# rt_hirose_breakout.net
KiCad netlist of a schematic drawn in EAGLE
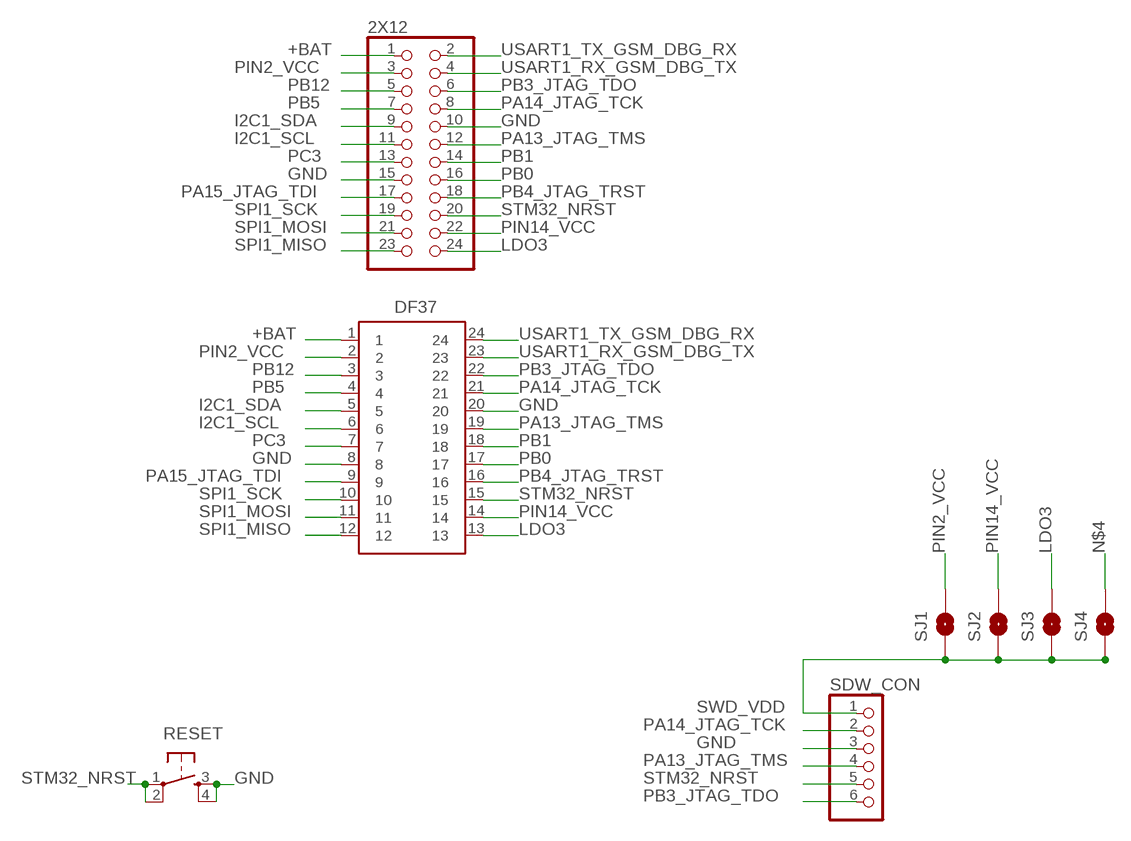
[diagram p0: schematic, sheet 1]

(export (version "E")
  (design (tool "Eeschema 10.0.6"))
  (components
    (comp (ref "2X12")
      (value "PINHD-2X12")
      (footprint "eagle-import:2X12")
      (libsource (lib "eagle-import") (part "PINHD-2X12"))
    )
    (comp (ref "DF37")
      (value "DF37-24-HEADER")
      (footprint "eagle-import:DF37-24-HEADER")
      (libsource (lib "eagle-import") (part "DF37-24-HEADER"))
    )
    (comp (ref "RESET")
      (value "TAC_SWITCHSMD")
      (footprint "eagle-import:TACTILE_SWITCH_SMD")
      (libsource (lib "eagle-import") (part "TAC_SWITCHSMD"))
    )
    (comp (ref "SDW_CON")
      (value "PINHD-1X6")
      (footprint "eagle-import:1X06")
      (libsource (lib "eagle-import") (part "PINHD-1X6"))
    )
    (comp (ref "SJ1")
      (value "SOLDERJUMPERNO")
      (footprint "eagle-import:SJ_2S-NO")
      (libsource (lib "eagle-import") (part "SOLDERJUMPERNO"))
    )
    (comp (ref "SJ2")
      (value "SOLDERJUMPERNO")
      (footprint "eagle-import:SJ_2S-NO")
      (libsource (lib "eagle-import") (part "SOLDERJUMPERNO"))
    )
    (comp (ref "SJ3")
      (value "SOLDERJUMPERNO")
      (footprint "eagle-import:SJ_2S-NO")
      (libsource (lib "eagle-import") (part "SOLDERJUMPERNO"))
    )
    (comp (ref "SJ4")
      (value "SOLDERJUMPERNO")
      (footprint "eagle-import:SJ_2S-NO")
      (libsource (lib "eagle-import") (part "SOLDERJUMPERNO"))
    )
  )
  (nets
    (net (code "1") (name "/+BAT") (class "Default")
      (node (ref "2X12") (pin "1") (pinfunction "1_1") (pintype "passive"))
      (node (ref "DF37") (pin "1") (pinfunction "1_1") (pintype "bidirectional"))
    )
    (net (code "2") (name "/GND") (class "Default")
      (node (ref "2X12") (pin "10") (pinfunction "10_10") (pintype "passive"))
      (node (ref "2X12") (pin "15") (pinfunction "15_15") (pintype "passive"))
      (node (ref "DF37") (pin "20") (pinfunction "20_20") (pintype "bidirectional"))
      (node (ref "DF37") (pin "8") (pinfunction "8_8") (pintype "bidirectional"))
      (node (ref "RESET") (pin "3") (pinfunction "3_3") (pintype "passive"))
      (node (ref "RESET") (pin "4") (pinfunction "4_4") (pintype "passive"))
      (node (ref "SDW_CON") (pin "3") (pinfunction "3_3") (pintype "passive"))
    )
    (net (code "3") (name "/I2C1_SCL") (class "Default")
      (node (ref "2X12") (pin "11") (pinfunction "11_11") (pintype "passive"))
      (node (ref "DF37") (pin "6") (pinfunction "6_6") (pintype "bidirectional"))
    )
    (net (code "4") (name "/I2C1_SDA") (class "Default")
      (node (ref "2X12") (pin "9") (pinfunction "9_9") (pintype "passive"))
      (node (ref "DF37") (pin "5") (pinfunction "5_5") (pintype "bidirectional"))
    )
    (net (code "5") (name "/LDO3") (class "Default")
      (node (ref "2X12") (pin "24") (pinfunction "24_24") (pintype "passive"))
      (node (ref "DF37") (pin "13") (pinfunction "13_13") (pintype "bidirectional"))
      (node (ref "SJ3") (pin "2") (pinfunction "2_2") (pintype "passive"))
    )
    (net (code "6") (name "/N$4") (class "Default")
      (node (ref "SJ4") (pin "2") (pinfunction "2_2") (pintype "passive"))
    )
    (net (code "7") (name "/PA13_JTAG_TMS") (class "Default")
      (node (ref "2X12") (pin "12") (pinfunction "12_12") (pintype "passive"))
      (node (ref "DF37") (pin "19") (pinfunction "19_19") (pintype "bidirectional"))
      (node (ref "SDW_CON") (pin "4") (pinfunction "4_4") (pintype "passive"))
    )
    (net (code "8") (name "/PA14_JTAG_TCK") (class "Default")
      (node (ref "2X12") (pin "8") (pinfunction "8_8") (pintype "passive"))
      (node (ref "DF37") (pin "21") (pinfunction "21_21") (pintype "bidirectional"))
      (node (ref "SDW_CON") (pin "2") (pinfunction "2_2") (pintype "passive"))
    )
    (net (code "9") (name "/PA15_JTAG_TDI") (class "Default")
      (node (ref "2X12") (pin "17") (pinfunction "17_17") (pintype "passive"))
      (node (ref "DF37") (pin "9") (pinfunction "9_9") (pintype "bidirectional"))
    )
    (net (code "10") (name "/PB0") (class "Default")
      (node (ref "2X12") (pin "16") (pinfunction "16_16") (pintype "passive"))
      (node (ref "DF37") (pin "17") (pinfunction "17_17") (pintype "bidirectional"))
    )
    (net (code "11") (name "/PB1") (class "Default")
      (node (ref "2X12") (pin "14") (pinfunction "14_14") (pintype "passive"))
      (node (ref "DF37") (pin "18") (pinfunction "18_18") (pintype "bidirectional"))
    )
    (net (code "12") (name "/PB3_JTAG_TDO") (class "Default")
      (node (ref "2X12") (pin "6") (pinfunction "6_6") (pintype "passive"))
      (node (ref "DF37") (pin "22") (pinfunction "22_22") (pintype "bidirectional"))
      (node (ref "SDW_CON") (pin "6") (pinfunction "6_6") (pintype "passive"))
    )
    (net (code "13") (name "/PB4_JTAG_TRST") (class "Default")
      (node (ref "2X12") (pin "18") (pinfunction "18_18") (pintype "passive"))
      (node (ref "DF37") (pin "16") (pinfunction "16_16") (pintype "bidirectional"))
    )
    (net (code "14") (name "/PB5") (class "Default")
      (node (ref "2X12") (pin "7") (pinfunction "7_7") (pintype "passive"))
      (node (ref "DF37") (pin "4") (pinfunction "4_4") (pintype "bidirectional"))
    )
    (net (code "15") (name "/PB12") (class "Default")
      (node (ref "2X12") (pin "5") (pinfunction "5_5") (pintype "passive"))
      (node (ref "DF37") (pin "3") (pinfunction "3_3") (pintype "bidirectional"))
    )
    (net (code "16") (name "/PC3") (class "Default")
      (node (ref "2X12") (pin "13") (pinfunction "13_13") (pintype "passive"))
      (node (ref "DF37") (pin "7") (pinfunction "7_7") (pintype "bidirectional"))
    )
    (net (code "17") (name "/PIN2_VCC") (class "Default")
      (node (ref "2X12") (pin "3") (pinfunction "3_3") (pintype "passive"))
      (node (ref "DF37") (pin "2") (pinfunction "2_2") (pintype "bidirectional"))
      (node (ref "SJ1") (pin "2") (pinfunction "2_2") (pintype "passive"))
    )
    (net (code "18") (name "/PIN14_VCC") (class "Default")
      (node (ref "2X12") (pin "22") (pinfunction "22_22") (pintype "passive"))
      (node (ref "DF37") (pin "14") (pinfunction "14_14") (pintype "bidirectional"))
      (node (ref "SJ2") (pin "2") (pinfunction "2_2") (pintype "passive"))
    )
    (net (code "19") (name "/SPI1_MISO") (class "Default")
      (node (ref "2X12") (pin "23") (pinfunction "23_23") (pintype "passive"))
      (node (ref "DF37") (pin "12") (pinfunction "12_12") (pintype "bidirectional"))
    )
    (net (code "20") (name "/SPI1_MOSI") (class "Default")
      (node (ref "2X12") (pin "21") (pinfunction "21_21") (pintype "passive"))
      (node (ref "DF37") (pin "11") (pinfunction "11_11") (pintype "bidirectional"))
    )
    (net (code "21") (name "/SPI1_SCK") (class "Default")
      (node (ref "2X12") (pin "19") (pinfunction "19_19") (pintype "passive"))
      (node (ref "DF37") (pin "10") (pinfunction "10_10") (pintype "bidirectional"))
    )
    (net (code "22") (name "/STM32_NRST") (class "Default")
      (node (ref "2X12") (pin "20") (pinfunction "20_20") (pintype "passive"))
      (node (ref "DF37") (pin "15") (pinfunction "15_15") (pintype "bidirectional"))
      (node (ref "RESET") (pin "1") (pinfunction "1_1") (pintype "passive"))
      (node (ref "RESET") (pin "2") (pinfunction "2_2") (pintype "passive"))
      (node (ref "SDW_CON") (pin "5") (pinfunction "5_5") (pintype "passive"))
    )
    (net (code "23") (name "/SWD_VDD") (class "Default")
      (node (ref "SDW_CON") (pin "1") (pinfunction "1_1") (pintype "passive"))
      (node (ref "SJ1") (pin "1") (pinfunction "1_1") (pintype "passive"))
      (node (ref "SJ2") (pin "1") (pinfunction "1_1") (pintype "passive"))
      (node (ref "SJ3") (pin "1") (pinfunction "1_1") (pintype "passive"))
      (node (ref "SJ4") (pin "1") (pinfunction "1_1") (pintype "passive"))
    )
    (net (code "24") (name "/USART1_RX_GSM_DBG_TX") (class "Default")
      (node (ref "2X12") (pin "4") (pinfunction "4_4") (pintype "passive"))
      (node (ref "DF37") (pin "23") (pinfunction "23_23") (pintype "bidirectional"))
    )
    (net (code "25") (name "/USART1_TX_GSM_DBG_RX") (class "Default")
      (node (ref "2X12") (pin "2") (pinfunction "2_2") (pintype "passive"))
      (node (ref "DF37") (pin "24") (pinfunction "24_24") (pintype "bidirectional"))
    )
  )
)
